# magnet.net
KiCad netlist of a schematic drawn in EAGLE
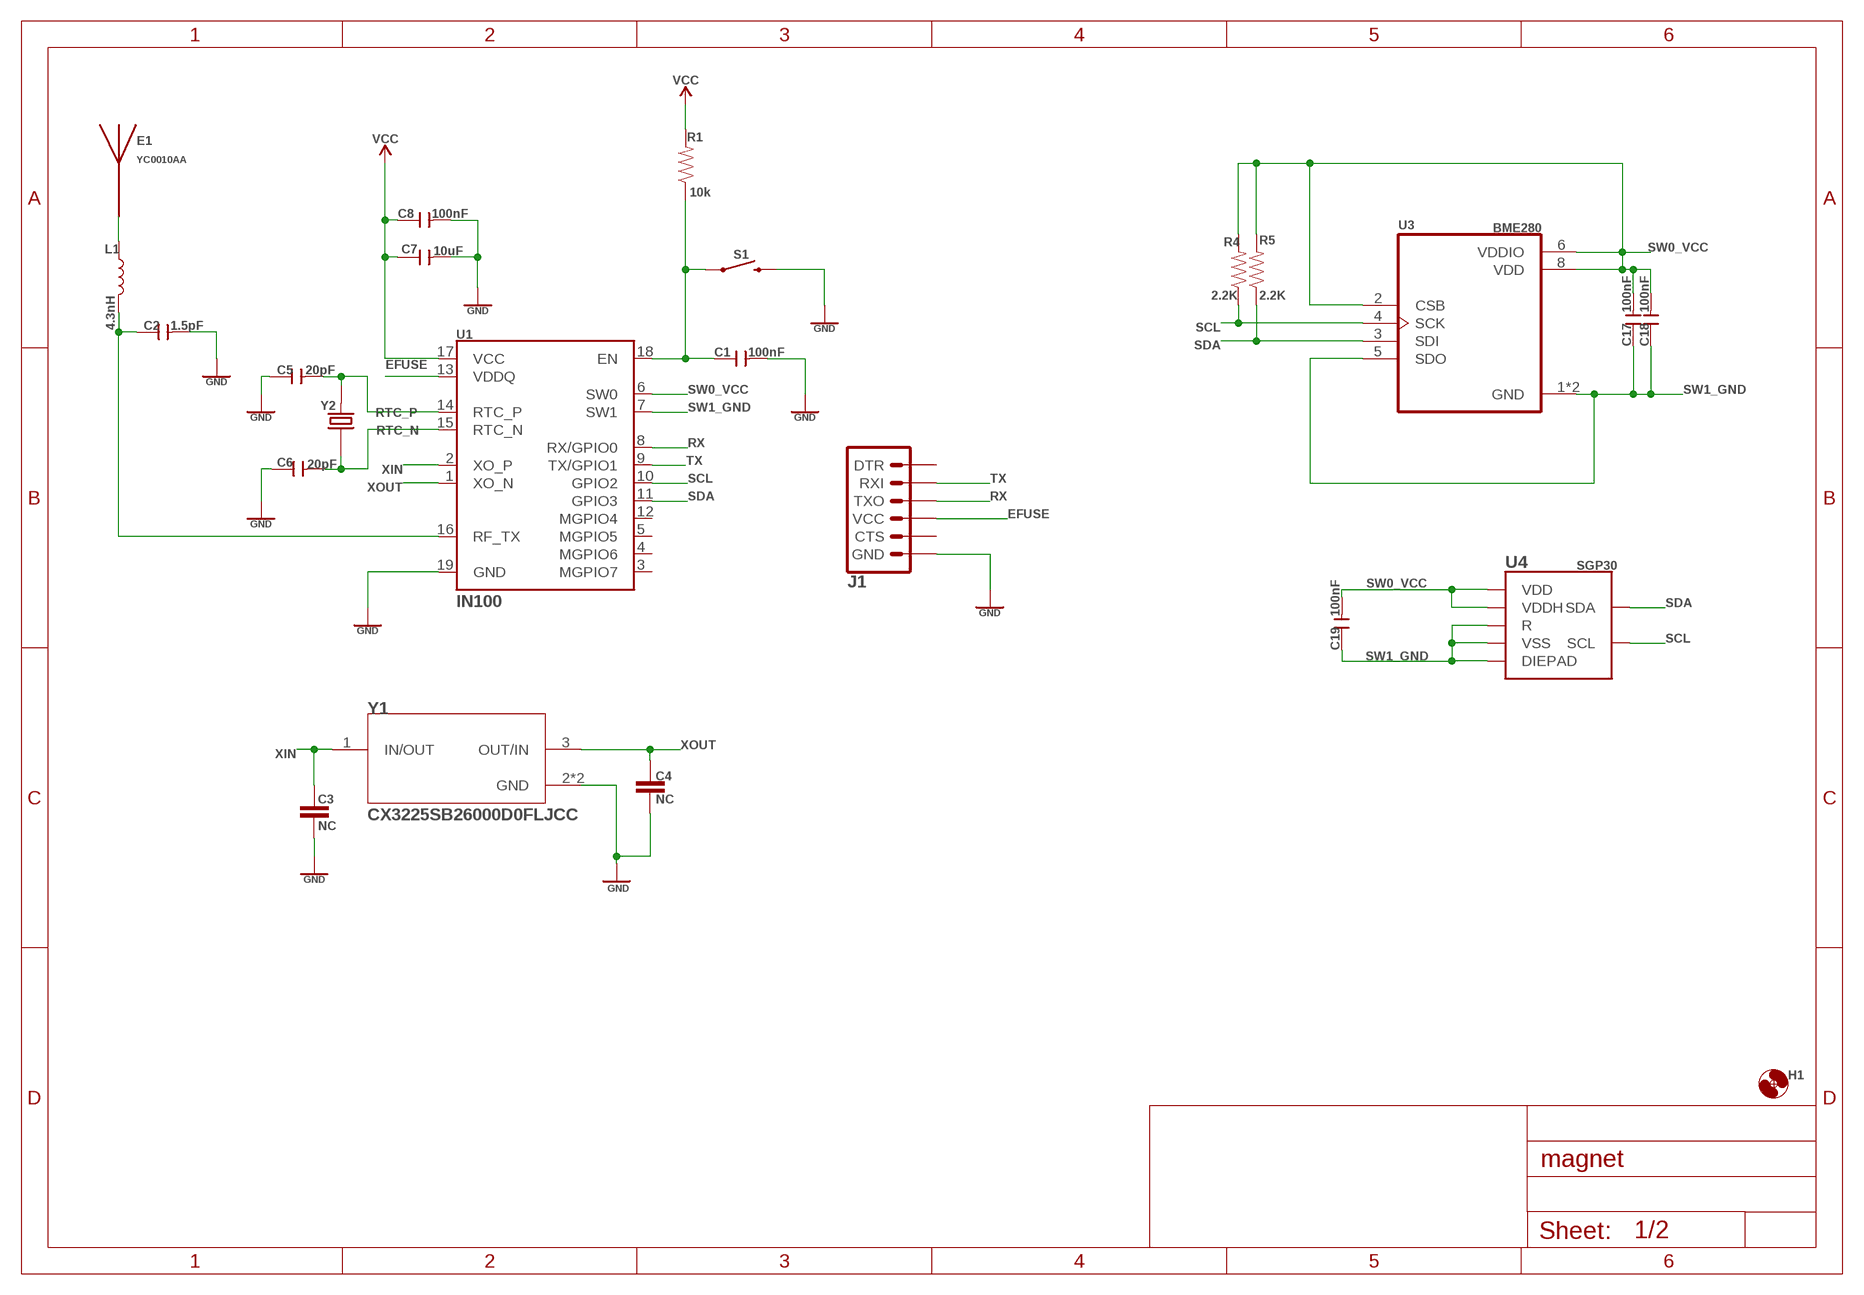
[diagram p0: schematic, sheet 1]
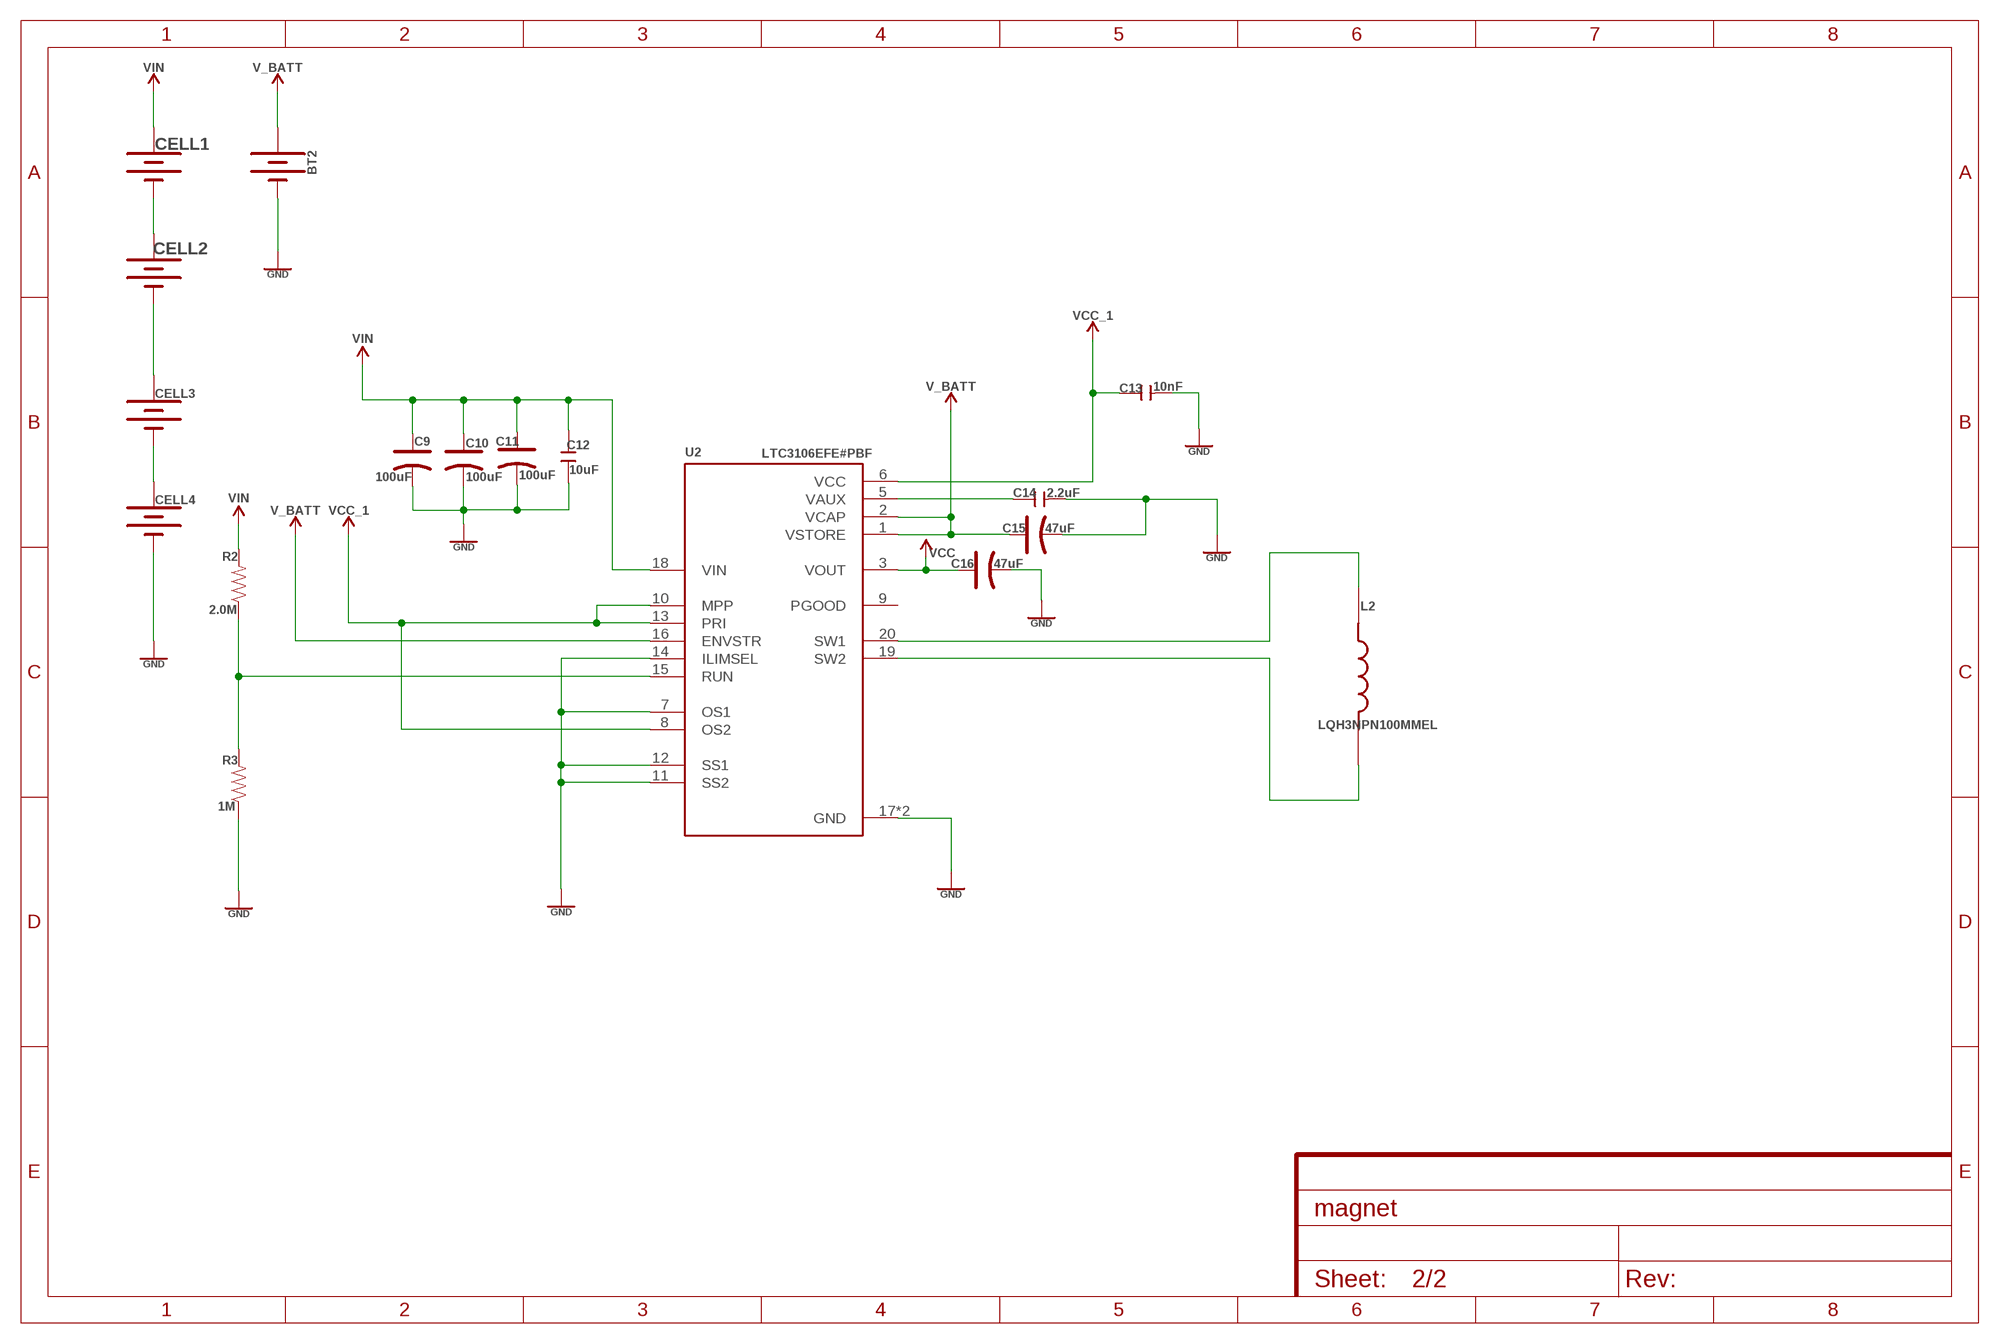
[diagram p1: schematic, sheet 2]

(export (version "E")
  (design (tool "Eeschema 10.0.6"))
  (components
    (comp (ref "BT2")
      (value "BATTERY-12MM_SMD")
      (footprint "eagle-import:BATTCON_12MM")
      (libsource (lib "eagle-import") (part "BATTERY-12MM_SMD"))
    )
    (comp (ref "C9")
      (value "100uF")
      (footprint "eagle-import:AVX-A")
      (fields (field (name "MPN") "TAJA476*006#NJ"))
      (libsource (lib "eagle-import") (part "TANTALUM-SMD-47UF-6.3V(AVX-A)"))
    )
    (comp (ref "C10")
      (value "100uF")
      (footprint "eagle-import:AVX-A")
      (fields (field (name "MPN") "TAJA476*006#NJ"))
      (libsource (lib "eagle-import") (part "TANTALUM-SMD-47UF-6.3V(AVX-A)"))
    )
    (comp (ref "C11")
      (value "100uF")
      (footprint "eagle-import:AVX-A")
      (fields (field (name "MPN") "TAJA476*006#NJ"))
      (libsource (lib "eagle-import") (part "TANTALUM-SMD-47UF-6.3V(AVX-A)"))
    )
    (comp (ref "C12")
      (value "10uF")
      (footprint "eagle-import:C0603")
      (fields (field (name "MPN") "CC0603MRX5R5BB106"))
      (libsource (lib "eagle-import") (part "CERAMIC-10UF-6.3V-20%-X5R(0603)"))
    )
    (comp (ref "C13")
      (value "10nF")
      (footprint "eagle-import:C0603")
      (fields (field (name "MPN") "CC0603KRX7R9BB103"))
      (libsource (lib "eagle-import") (part "CERAMIC-10NF-50V-10%-X7R(0603)"))
    )
    (comp (ref "C14")
      (value "2.2uF")
      (footprint "eagle-import:C0603")
      (fields (field (name "MPN") "CC0603KRX7R6BB225"))
      (libsource (lib "eagle-import") (part "CERAMIC-2.2UF-10V-10%-X7R(0603)"))
    )
    (comp (ref "C15")
      (value "47uF")
      (footprint "eagle-import:AVX-A")
      (fields (field (name "MPN") "TAJA476*006#NJ"))
      (libsource (lib "eagle-import") (part "TANTALUM-SMD-47UF-6.3V(AVX-A)"))
    )
    (comp (ref "C16")
      (value "47uF")
      (footprint "eagle-import:AVX-A")
      (fields (field (name "MPN") "TAJA476*006#NJ"))
      (libsource (lib "eagle-import") (part "TANTALUM-SMD-47UF-6.3V(AVX-A)"))
    )
    (comp (ref "CELL1")
      (value "KXOB25")
      (footprint "eagle-import:KXOB25")
      (libsource (lib "eagle-import") (part "KXOB25"))
    )
    (comp (ref "CELL2")
      (value "KXOB25")
      (footprint "eagle-import:KXOB25")
      (libsource (lib "eagle-import") (part "KXOB25"))
    )
    (comp (ref "CELL3")
      (value "KXOB25")
      (footprint "eagle-import:KXOB25")
      (libsource (lib "eagle-import") (part "KXOB25"))
    )
    (comp (ref "CELL4")
      (value "KXOB25")
      (footprint "eagle-import:KXOB25")
      (libsource (lib "eagle-import") (part "KXOB25"))
    )
    (comp (ref "L2")
      (value "LQH3NPN100MMEL")
      (footprint "eagle-import:IND_LQH3NPN100MMEL")
      (fields (field (name "DIGI-KEY_PART_NUMBER") "490-15945-1-ND") (field (name "MF") "Murata"))
      (libsource (lib "eagle-import") (part "LQH3NPN100MMEL"))
    )
    (comp (ref "R2")
      (value "2.0M")
      (footprint "eagle-import:0603")
      (libsource (lib "eagle-import") (part "2MOHMS-0603-1/10W-1%"))
    )
    (comp (ref "R3")
      (value "1M")
      (footprint "eagle-import:0603")
      (libsource (lib "eagle-import") (part "1MOHM-0603-1/4W-5%"))
    )
    (comp (ref "U2")
      (value "LTC3106EFE#PBF")
      (footprint "eagle-import:SOP65P640X120-21N")
      (fields (field (name "MF") "Analog Devices"))
      (libsource (lib "eagle-import") (part "LTC3106EFE#PBF"))
    )
    (comp (ref "C1")
      (value "100nF")
      (footprint "eagle-import:C0603")
      (fields (field (name "MPN") "CC0603KRX7R9BB104"))
      (libsource (lib "eagle-import") (part "CERAMIC-100NF-50V-10%-X7R(0603)"))
    )
    (comp (ref "C2")
      (value "1.5pF")
      (footprint "eagle-import:C0603")
      (fields (field (name "MPN") "CC0603JRNPO9BN100"))
      (libsource (lib "eagle-import") (part "CERAMIC-10PF-50V-5%-NPO(0603)"))
    )
    (comp (ref "C3")
      (value "NC")
      (footprint "eagle-import:0603")
      (libsource (lib "eagle-import") (part "12PF-0603-50V-5%"))
    )
    (comp (ref "C4")
      (value "NC")
      (footprint "eagle-import:0603")
      (libsource (lib "eagle-import") (part "12PF-0603-50V-5%"))
    )
    (comp (ref "C5")
      (value "20pF")
      (footprint "eagle-import:C0603")
      (fields (field (name "MPN") "CC0603JRNPO9BN220"))
      (libsource (lib "eagle-import") (part "CERAMIC-22PF-50V-5%-NPO(0603)"))
    )
    (comp (ref "C6")
      (value "20pF")
      (footprint "eagle-import:C0603")
      (fields (field (name "MPN") "CC0603JRNPO9BN220"))
      (libsource (lib "eagle-import") (part "CERAMIC-22PF-50V-5%-NPO(0603)"))
    )
    (comp (ref "C7")
      (value "10uF")
      (footprint "eagle-import:C0603")
      (fields (field (name "MPN") "CC0603KRX5R6BB106"))
      (libsource (lib "eagle-import") (part "CERAMIC-10UF-10V-10%-X5R(0603)"))
    )
    (comp (ref "C8")
      (value "100nF")
      (footprint "eagle-import:C0603")
      (fields (field (name "MPN") "CC0603KRX7R9BB104"))
      (libsource (lib "eagle-import") (part "CERAMIC-100NF-50V-10%-X7R(0603)"))
    )
    (comp (ref "C17")
      (value "100nF")
      (footprint "eagle-import:C0603")
      (fields (field (name "MPN") "CC0603KRX7R9BB104"))
      (libsource (lib "eagle-import") (part "CERAMIC-100NF-50V-10%-X7R(0603)"))
    )
    (comp (ref "C18")
      (value "100nF")
      (footprint "eagle-import:C0603")
      (fields (field (name "MPN") "CC0603KRX7R9BB104"))
      (libsource (lib "eagle-import") (part "CERAMIC-100NF-50V-10%-X7R(0603)"))
    )
    (comp (ref "C19")
      (value "100nF")
      (footprint "eagle-import:C0603")
      (fields (field (name "MPN") "CC0603KRX7R9BB104"))
      (libsource (lib "eagle-import") (part "CERAMIC-100NF-50V-10%-X7R(0603)"))
    )
    (comp (ref "E1")
      (value "YC0010AA")
      (footprint "eagle-import:XCVR_YC0010AA")
      (fields (field (name "MF") "Quectel"))
      (libsource (lib "eagle-import") (part "YC0010AA"))
    )
    (comp (ref "H1")
      (value "MOUNT-HOLE3.0")
      (footprint "eagle-import:3,0")
      (libsource (lib "eagle-import") (part "MOUNT-HOLE3.0"))
    )
    (comp (ref "J1")
      (value "6_PIN_SERIAL_TARGETSMD")
      (footprint "eagle-import:1X06-SMD_RA_MALE")
      (libsource (lib "eagle-import") (part "6_PIN_SERIAL_TARGETSMD"))
    )
    (comp (ref "L1")
      (value "4.3nH")
      (footprint "eagle-import:0603")
      (libsource (lib "eagle-import") (part "INDUCTOR-0603-33NH"))
    )
    (comp (ref "R1")
      (value "10k")
      (footprint "eagle-import:0603")
      (libsource (lib "eagle-import") (part "10KOHM-0603-1/10W-1%"))
    )
    (comp (ref "R4")
      (value "2.2K")
      (footprint "eagle-import:0603")
      (libsource (lib "eagle-import") (part "2.2KOHM-0603-1/10W-1%"))
    )
    (comp (ref "R5")
      (value "2.2K")
      (footprint "eagle-import:0603")
      (libsource (lib "eagle-import") (part "2.2KOHM-0603-1/10W-1%"))
    )
    (comp (ref "S1")
      (value "MOMENTARY-SWITCH-SPST-SMD-4.6X2.8MM")
      (footprint "eagle-import:TACTILE_SWITCH_SMD_4.6X2.8MM")
      (libsource (lib "eagle-import") (part "MOMENTARY-SWITCH-SPST-SMD-4.6X2.8MM"))
    )
    (comp (ref "U1")
      (value "IN100")
      (footprint "eagle-import:IN100")
      (libsource (lib "eagle-import") (part "IN100"))
    )
    (comp (ref "U3")
      (value "BME280")
      (footprint "eagle-import:PSON65P250X250X100-8N")
      (fields (field (name "MF") "Bosch"))
      (libsource (lib "eagle-import") (part "BME280"))
    )
    (comp (ref "U4")
      (value "SGP30")
      (footprint "eagle-import:SGP30")
      (fields (field (name "MF") "Sensirion AG"))
      (libsource (lib "eagle-import") (part "SGP30"))
    )
    (comp (ref "Y1")
      (value "CX3225SB26000D0FLJCC")
      (footprint "eagle-import:XTAL_ECS-480-8-33B-CWY-TR3")
      (fields
        (field (name "MF") "ECS Inc.")
        (field (name "MP") "ECS-480-8-33B-CWY-TR3")
        (field (name "MF_1") "Kyocera")
        (field (name "MP_1") "CX3225SB26000D0FLJCC")
      )
      (libsource (lib "eagle-import") (part "ECS-480-8-33B-CWY-TR3"))
    )
    (comp (ref "Y2")
      (value "ECS-.327-12.5-16-TR")
      (footprint "eagle-import:XTAL_ECS-.327-12.5-16-TR")
      (fields (field (name "MF") "ECS Inc."))
      (libsource (lib "eagle-import") (part "ECS-.327-12.5-16-TR"))
    )
  )
  (nets
    (net (code "1") (name "EFUSE") (class "Default")
      (node (ref "J1") (pin "4") (pinfunction "VCC_4") (pintype "passive"))
      (node (ref "U1") (pin "13") (pinfunction "VDDQ_13") (pintype "power_in"))
    )
    (net (code "2") (name "GND") (class "Default")
      (node (ref "BT2") (pin "GND") (pinfunction "-_GND") (pintype "power_in"))
      (node (ref "C1") (pin "2") (pinfunction "2_2") (pintype "passive"))
      (node (ref "C10") (pin "-") (pinfunction "-_-") (pintype "passive"))
      (node (ref "C11") (pin "-") (pinfunction "-_-") (pintype "passive"))
      (node (ref "C12") (pin "1") (pinfunction "1_1") (pintype "passive"))
      (node (ref "C13") (pin "2") (pinfunction "2_2") (pintype "passive"))
      (node (ref "C14") (pin "2") (pinfunction "2_2") (pintype "passive"))
      (node (ref "C15") (pin "-") (pinfunction "-_-") (pintype "passive"))
      (node (ref "C16") (pin "-") (pinfunction "-_-") (pintype "passive"))
      (node (ref "C2") (pin "2") (pinfunction "2_2") (pintype "passive"))
      (node (ref "C3") (pin "2") (pinfunction "2_2") (pintype "passive"))
      (node (ref "C4") (pin "2") (pinfunction "2_2") (pintype "passive"))
      (node (ref "C5") (pin "1") (pinfunction "1_1") (pintype "passive"))
      (node (ref "C6") (pin "1") (pinfunction "1_1") (pintype "passive"))
      (node (ref "C7") (pin "2") (pinfunction "2_2") (pintype "passive"))
      (node (ref "C8") (pin "2") (pinfunction "2_2") (pintype "passive"))
      (node (ref "C9") (pin "-") (pinfunction "-_-") (pintype "passive"))
      (node (ref "CELL4") (pin "-") (pinfunction "-_-") (pintype "power_in"))
      (node (ref "J1") (pin "6") (pinfunction "GND_6") (pintype "passive"))
      (node (ref "R3") (pin "1") (pinfunction "1_1") (pintype "passive"))
      (node (ref "S1") (pin "3") (pinfunction "2_3") (pintype "passive"))
      (node (ref "S1") (pin "4") (pinfunction "2_4") (pintype "passive"))
      (node (ref "U1") (pin "19") (pinfunction "GND_19") (pintype "power_in"))
      (node (ref "U2") (pin "11") (pinfunction "SS2_11") (pintype "input"))
      (node (ref "U2") (pin "12") (pinfunction "SS1_12") (pintype "input"))
      (node (ref "U2") (pin "14") (pinfunction "ILIMSEL_14") (pintype "input"))
      (node (ref "U2") (pin "17") (pinfunction "GND_17") (pintype "power_in"))
      (node (ref "U2") (pin "21") (pinfunction "GND_21") (pintype "power_in"))
      (node (ref "U2") (pin "7") (pinfunction "OS1_7") (pintype "input"))
      (node (ref "Y1") (pin "2") (pinfunction "GND_2") (pintype "power_in"))
      (node (ref "Y1") (pin "4") (pinfunction "GND_4") (pintype "power_in"))
    )
    (net (code "3") (name "Net-(CELL1-Pad-)") (class "Default")
      (node (ref "CELL1") (pin "-") (pinfunction "-_-") (pintype "power_in"))
      (node (ref "CELL2") (pin "+") (pinfunction "+_+") (pintype "power_in"))
    )
    (net (code "4") (name "Net-(CELL2-Pad-)") (class "Default")
      (node (ref "CELL2") (pin "-") (pinfunction "-_-") (pintype "power_in"))
      (node (ref "CELL3") (pin "+") (pinfunction "+_+") (pintype "power_in"))
    )
    (net (code "5") (name "Net-(CELL3-Pad-)") (class "Default")
      (node (ref "CELL3") (pin "-") (pinfunction "-_-") (pintype "power_in"))
      (node (ref "CELL4") (pin "+") (pinfunction "+_+") (pintype "power_in"))
    )
    (net (code "6") (name "Net-(E1-Pad1)") (class "Default")
      (node (ref "E1") (pin "1") (pinfunction "1_1") (pintype "input"))
      (node (ref "L1") (pin "1") (pinfunction "1_1") (pintype "passive"))
    )
    (net (code "7") (name "Net-(U1-EN)") (class "Default")
      (node (ref "C1") (pin "1") (pinfunction "1_1") (pintype "passive"))
      (node (ref "R1") (pin "1") (pinfunction "1_1") (pintype "passive"))
      (node (ref "S1") (pin "1") (pinfunction "1_1") (pintype "passive"))
      (node (ref "S1") (pin "2") (pinfunction "1_2") (pintype "passive"))
      (node (ref "U1") (pin "18") (pinfunction "EN_18") (pintype "input"))
    )
    (net (code "8") (name "Net-(U1-RF_TX)") (class "Default")
      (node (ref "C2") (pin "1") (pinfunction "1_1") (pintype "passive"))
      (node (ref "L1") (pin "2") (pinfunction "2_2") (pintype "passive"))
      (node (ref "U1") (pin "16") (pinfunction "RF_TX_16") (pintype "bidirectional"))
    )
    (net (code "9") (name "Net-(U2-RUN)") (class "Default")
      (node (ref "R2") (pin "1") (pinfunction "1_1") (pintype "passive"))
      (node (ref "R3") (pin "2") (pinfunction "2_2") (pintype "passive"))
      (node (ref "U2") (pin "15") (pinfunction "RUN_15") (pintype "input"))
    )
    (net (code "10") (name "Net-(U2-SW1)") (class "Default")
      (node (ref "L2") (pin "1") (pinfunction "1_1") (pintype "passive"))
      (node (ref "U2") (pin "20") (pinfunction "SW1_20") (pintype "passive"))
    )
    (net (code "11") (name "Net-(U2-SW2)") (class "Default")
      (node (ref "L2") (pin "2") (pinfunction "2_2") (pintype "passive"))
      (node (ref "U2") (pin "19") (pinfunction "SW2_19") (pintype "passive"))
    )
    (net (code "12") (name "Net-(U2-VAUX)") (class "Default")
      (node (ref "C14") (pin "1") (pinfunction "1_1") (pintype "passive"))
      (node (ref "U2") (pin "5") (pinfunction "VAUX_5") (pintype "power_in"))
    )
    (net (code "13") (name "RTC_N") (class "Default")
      (node (ref "C6") (pin "2") (pinfunction "2_2") (pintype "passive"))
      (node (ref "U1") (pin "15") (pinfunction "RTC_N_15") (pintype "bidirectional"))
      (node (ref "Y2") (pin "1") (pinfunction "1_1") (pintype "passive"))
    )
    (net (code "14") (name "RTC_P") (class "Default")
      (node (ref "C5") (pin "2") (pinfunction "2_2") (pintype "passive"))
      (node (ref "U1") (pin "14") (pinfunction "RTC_P_14") (pintype "bidirectional"))
      (node (ref "Y2") (pin "2") (pinfunction "2_2") (pintype "passive"))
    )
    (net (code "15") (name "RX") (class "Default")
      (node (ref "J1") (pin "3") (pinfunction "TXO_3") (pintype "passive"))
      (node (ref "U1") (pin "8") (pinfunction "RX/GPIO0_8") (pintype "bidirectional"))
    )
    (net (code "16") (name "SCL") (class "Default")
      (node (ref "R4") (pin "1") (pinfunction "1_1") (pintype "passive"))
      (node (ref "U1") (pin "10") (pinfunction "GPIO2_10") (pintype "bidirectional"))
      (node (ref "U3") (pin "4") (pinfunction "SCK_4") (pintype "input"))
      (node (ref "U4") (pin "6") (pinfunction "SCL_6") (pintype "bidirectional"))
    )
    (net (code "17") (name "SDA") (class "Default")
      (node (ref "R5") (pin "1") (pinfunction "1_1") (pintype "passive"))
      (node (ref "U1") (pin "11") (pinfunction "GPIO3_11") (pintype "bidirectional"))
      (node (ref "U3") (pin "3") (pinfunction "SDI_3") (pintype "bidirectional"))
      (node (ref "U4") (pin "3") (pinfunction "SDA_3") (pintype "bidirectional"))
    )
    (net (code "18") (name "SW0_VCC") (class "Default")
      (node (ref "C17") (pin "2") (pinfunction "2_2") (pintype "passive"))
      (node (ref "C18") (pin "2") (pinfunction "2_2") (pintype "passive"))
      (node (ref "C19") (pin "2") (pinfunction "2_2") (pintype "passive"))
      (node (ref "R4") (pin "2") (pinfunction "2_2") (pintype "passive"))
      (node (ref "R5") (pin "2") (pinfunction "2_2") (pintype "passive"))
      (node (ref "U1") (pin "6") (pinfunction "SW0_6") (pintype "output"))
      (node (ref "U3") (pin "2") (pinfunction "CSB_2") (pintype "input"))
      (node (ref "U3") (pin "6") (pinfunction "VDDIO_6") (pintype "power_in"))
      (node (ref "U3") (pin "8") (pinfunction "VDD_8") (pintype "power_in"))
      (node (ref "U4") (pin "1") (pinfunction "VDD_1") (pintype "bidirectional"))
      (node (ref "U4") (pin "5") (pinfunction "VDDH_5") (pintype "bidirectional"))
    )
    (net (code "19") (name "SW1_GND") (class "Default")
      (node (ref "C17") (pin "1") (pinfunction "1_1") (pintype "passive"))
      (node (ref "C18") (pin "1") (pinfunction "1_1") (pintype "passive"))
      (node (ref "C19") (pin "1") (pinfunction "1_1") (pintype "passive"))
      (node (ref "U1") (pin "7") (pinfunction "SW1_7") (pintype "output"))
      (node (ref "U3") (pin "1") (pinfunction "GND_1") (pintype "power_in"))
      (node (ref "U3") (pin "5") (pinfunction "SDO_5") (pintype "bidirectional"))
      (node (ref "U3") (pin "7") (pinfunction "GND_7") (pintype "power_in"))
      (node (ref "U4") (pin "2") (pinfunction "VSS_2") (pintype "bidirectional"))
      (node (ref "U4") (pin "4") (pinfunction "R_4") (pintype "bidirectional"))
      (node (ref "U4") (pin "DIEPAD") (pinfunction "DIEPAD_DIEPAD") (pintype "bidirectional"))
    )
    (net (code "20") (name "TX") (class "Default")
      (node (ref "J1") (pin "2") (pinfunction "RXI_2") (pintype "passive"))
      (node (ref "U1") (pin "9") (pinfunction "TX/GPIO1_9") (pintype "bidirectional"))
    )
    (net (code "21") (name "VCC") (class "Default")
      (node (ref "C16") (pin "+") (pinfunction "+_+") (pintype "passive"))
      (node (ref "C7") (pin "1") (pinfunction "1_1") (pintype "passive"))
      (node (ref "C8") (pin "1") (pinfunction "1_1") (pintype "passive"))
      (node (ref "R1") (pin "2") (pinfunction "2_2") (pintype "passive"))
      (node (ref "U1") (pin "17") (pinfunction "VCC_17") (pintype "power_in"))
      (node (ref "U2") (pin "3") (pinfunction "VOUT_3") (pintype "output"))
    )
    (net (code "22") (name "VCC_1") (class "Default")
      (node (ref "C13") (pin "1") (pinfunction "1_1") (pintype "passive"))
      (node (ref "U2") (pin "10") (pinfunction "MPP_10") (pintype "input"))
      (node (ref "U2") (pin "13") (pinfunction "PRI_13") (pintype "input"))
      (node (ref "U2") (pin "6") (pinfunction "VCC_6") (pintype "power_in"))
      (node (ref "U2") (pin "8") (pinfunction "OS2_8") (pintype "input"))
    )
    (net (code "23") (name "VIN") (class "Default")
      (node (ref "C10") (pin "+") (pinfunction "+_+") (pintype "passive"))
      (node (ref "C11") (pin "+") (pinfunction "+_+") (pintype "passive"))
      (node (ref "C12") (pin "2") (pinfunction "2_2") (pintype "passive"))
      (node (ref "C9") (pin "+") (pinfunction "+_+") (pintype "passive"))
      (node (ref "CELL1") (pin "+") (pinfunction "+_+") (pintype "power_in"))
      (node (ref "R2") (pin "2") (pinfunction "2_2") (pintype "passive"))
      (node (ref "U2") (pin "18") (pinfunction "VIN_18") (pintype "input"))
    )
    (net (code "24") (name "V_BATT") (class "Default")
      (node (ref "BT2") (pin "PWR@1") (pinfunction "+_PWR@1") (pintype "power_in"))
      (node (ref "C15") (pin "+") (pinfunction "+_+") (pintype "passive"))
      (node (ref "U2") (pin "1") (pinfunction "VSTORE_1") (pintype "power_in"))
      (node (ref "U2") (pin "16") (pinfunction "ENVSTR_16") (pintype "input"))
      (node (ref "U2") (pin "2") (pinfunction "VCAP_2") (pintype "power_in"))
    )
    (net (code "25") (name "XIN") (class "Default")
      (node (ref "C3") (pin "1") (pinfunction "1_1") (pintype "passive"))
      (node (ref "U1") (pin "2") (pinfunction "XO_P_2") (pintype "bidirectional"))
      (node (ref "Y1") (pin "1") (pinfunction "IN/OUT_1") (pintype "bidirectional"))
    )
    (net (code "26") (name "XOUT") (class "Default")
      (node (ref "C4") (pin "1") (pinfunction "1_1") (pintype "passive"))
      (node (ref "U1") (pin "1") (pinfunction "XO_N_1") (pintype "bidirectional"))
      (node (ref "Y1") (pin "3") (pinfunction "OUT/IN_3") (pintype "bidirectional"))
    )
    (net (code "27") (name "unconnected-(J1-CTS-Pad5)") (class "Default")
      (node (ref "J1") (pin "5") (pinfunction "CTS_5") (pintype "passive"))
    )
    (net (code "28") (name "unconnected-(J1-DTR-Pad1)") (class "Default")
      (node (ref "J1") (pin "1") (pinfunction "DTR_1") (pintype "passive"))
    )
    (net (code "29") (name "unconnected-(U1-MGPIO4-Pad12)") (class "Default")
      (node (ref "U1") (pin "12") (pinfunction "MGPIO4_12") (pintype "bidirectional"))
    )
    (net (code "30") (name "unconnected-(U1-MGPIO5-Pad5)") (class "Default")
      (node (ref "U1") (pin "5") (pinfunction "MGPIO5_5") (pintype "bidirectional"))
    )
    (net (code "31") (name "unconnected-(U1-MGPIO6-Pad4)") (class "Default")
      (node (ref "U1") (pin "4") (pinfunction "MGPIO6_4") (pintype "bidirectional"))
    )
    (net (code "32") (name "unconnected-(U1-MGPIO7-Pad3)") (class "Default")
      (node (ref "U1") (pin "3") (pinfunction "MGPIO7_3") (pintype "bidirectional"))
    )
    (net (code "33") (name "unconnected-(U2-PGOOD-Pad9)") (class "Default")
      (node (ref "U2") (pin "9") (pinfunction "PGOOD_9") (pintype "output"))
    )
  )
)
